# HBridge.net
KiCad netlist of a schematic drawn in Altium Designer
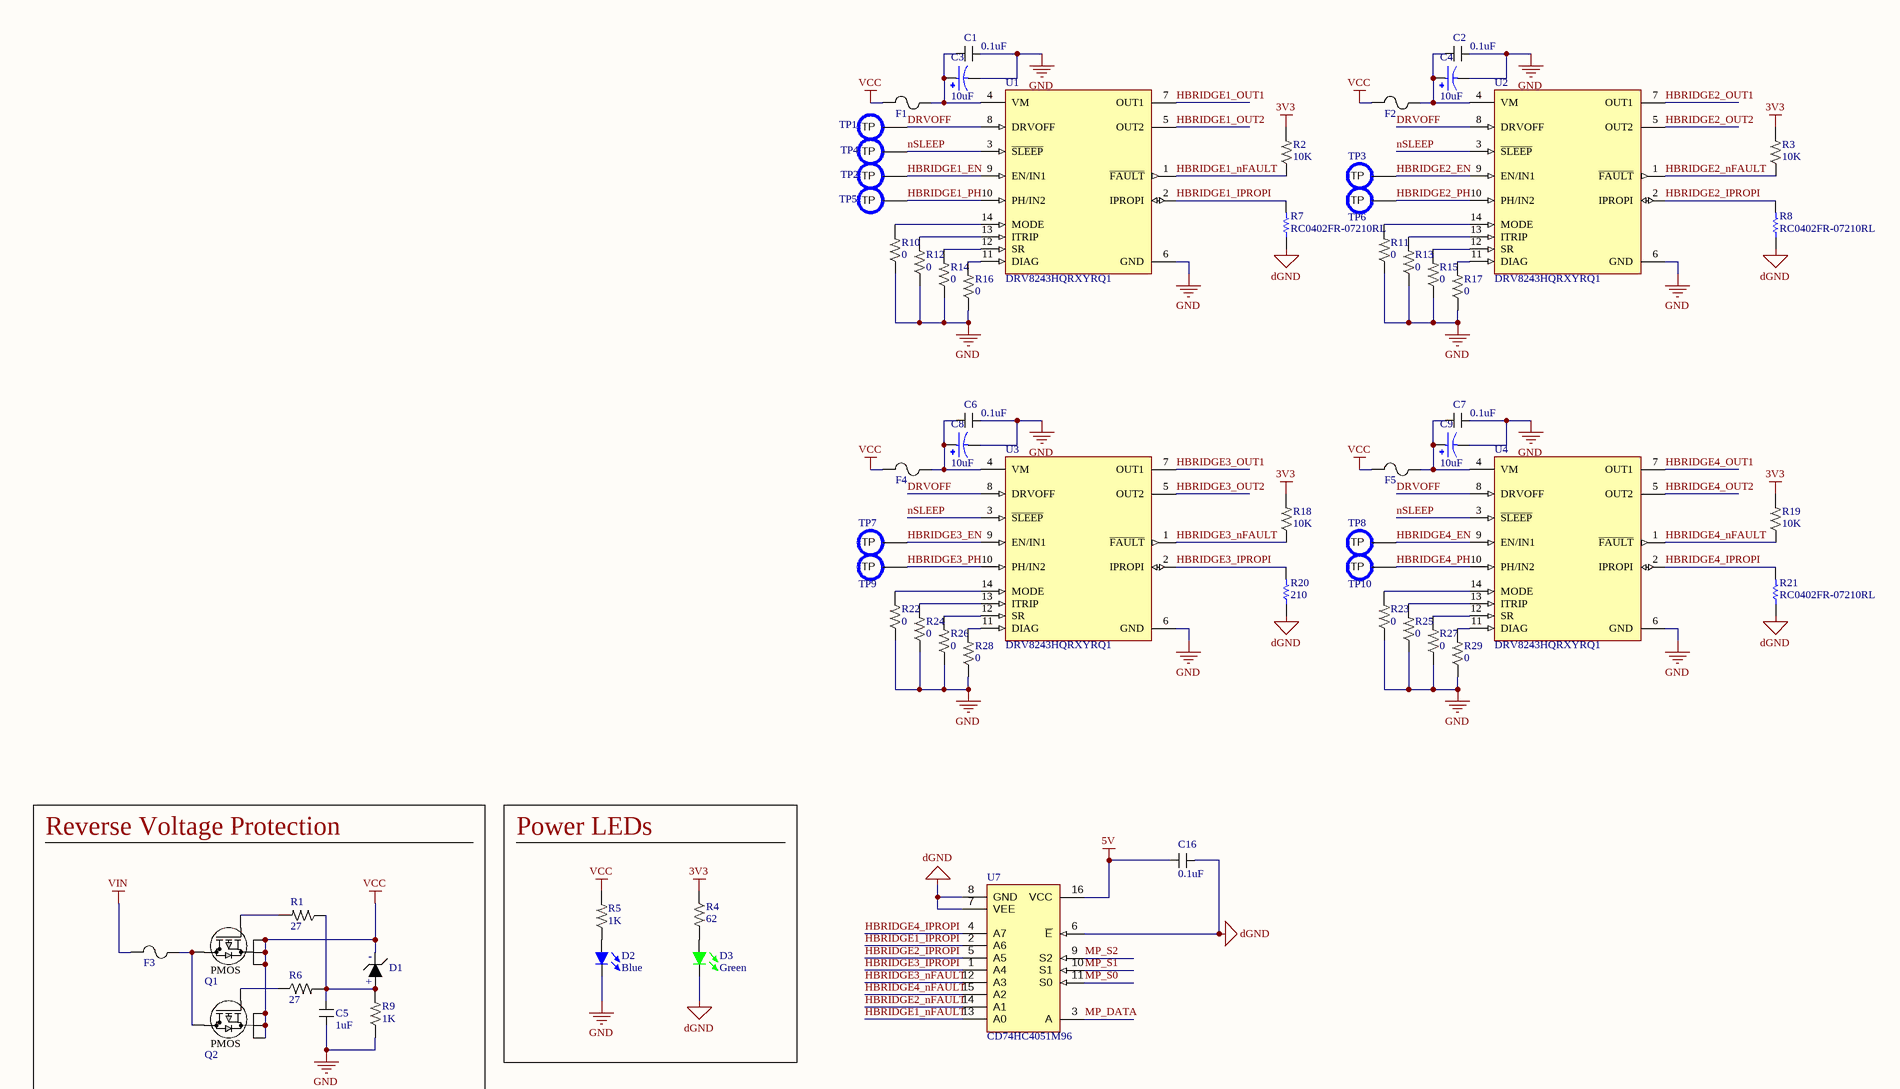
[diagram p0: HBridge.SchDoc, top left]
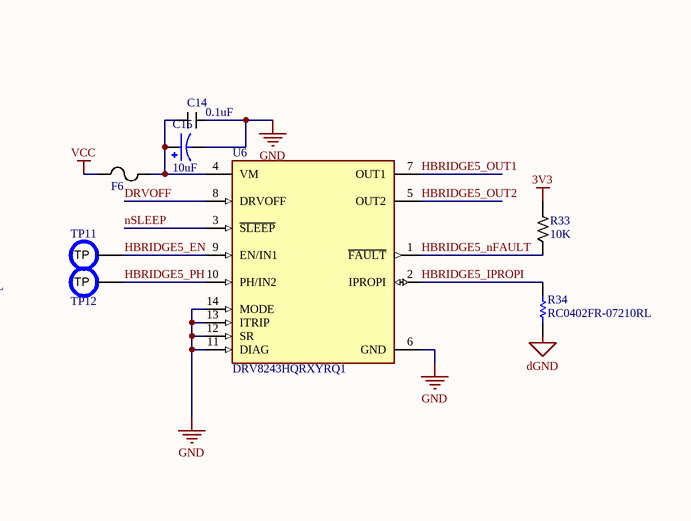
[diagram p1: HBridge.SchDoc, top right]
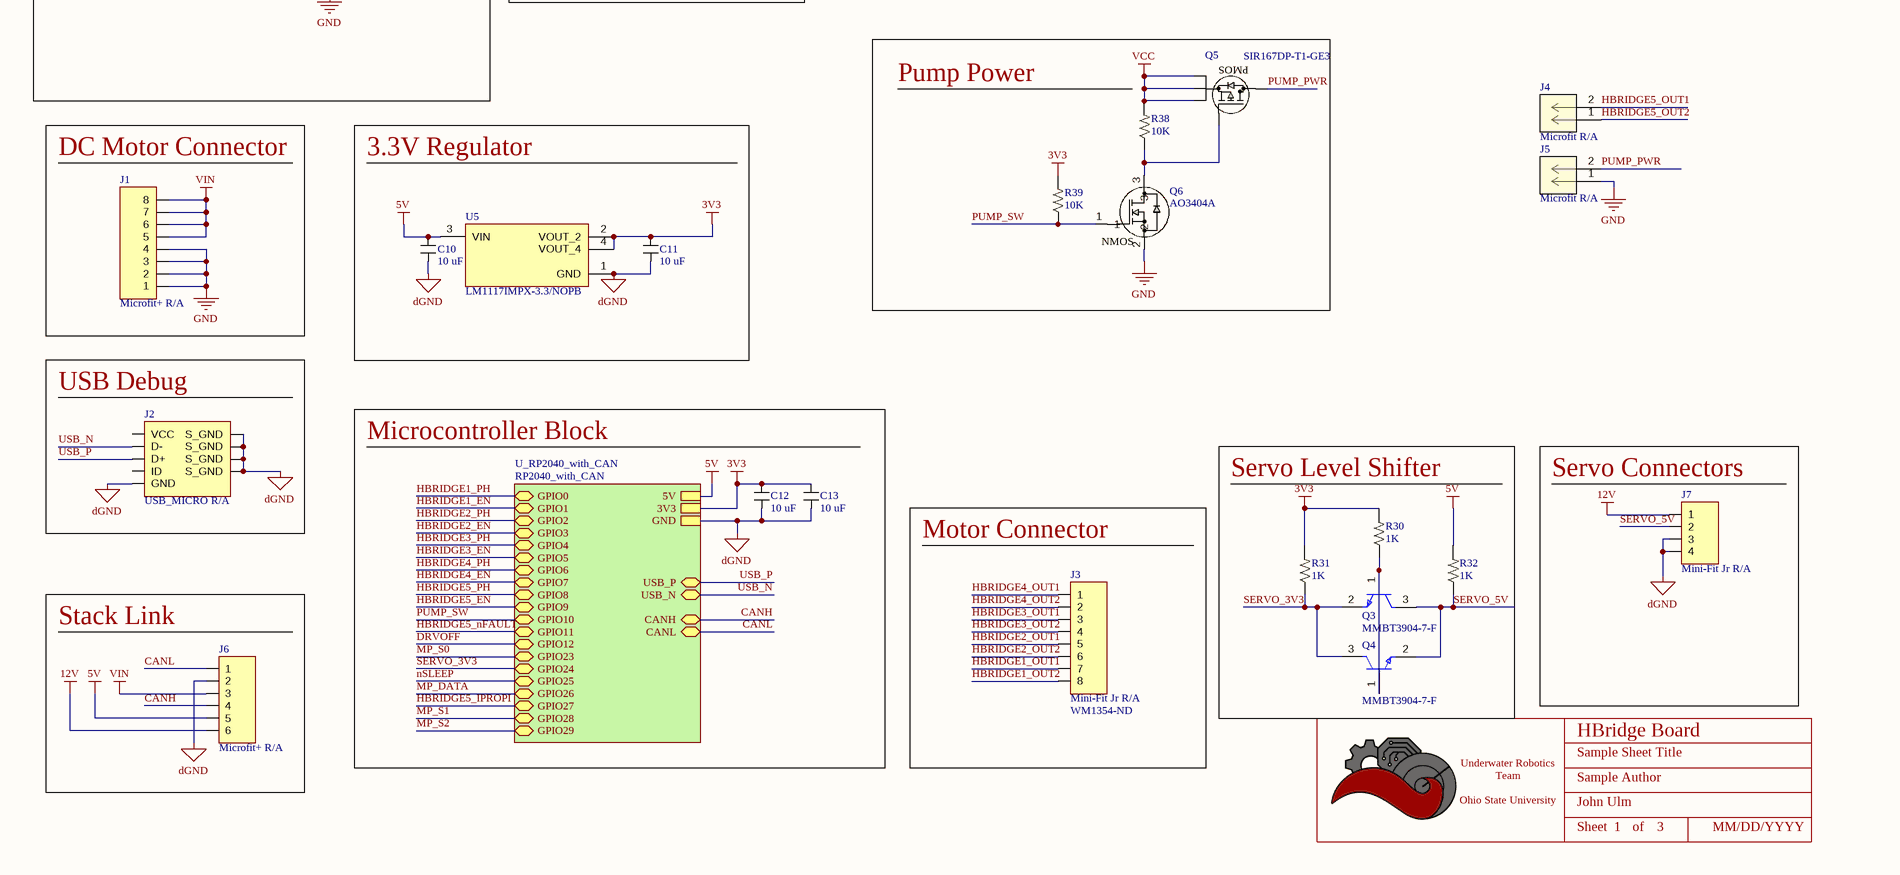
[diagram p2: HBridge.SchDoc, bottom left]

(export (version "E")
  (design (tool "Eeschema 10.0.6"))
  (components
    (comp (ref "*")
      (value "Title_Block")
      (footprint "LOGO")
      (description "UWRT Schematic Title Block Template\r\n\r\nCreated June 2021, Dylan Trainor")
      (libsource (lib "UWRT") (part "Title_Block"))
    )
    (comp (ref "C1")
      (value "0.1uF")
      (footprint "CAPACITOR_0805")
      (description "Cap 100nF 50V +/-10%\r\nCeramic 0805")
      (fields (field (name "TOLERANCE") "+/- 10%") (field (name "VOLTAGE") "50V"))
      (libsource (lib "Capacitors") (part "CAPACITOR_0.1uF_0805"))
    )
    (comp (ref "C2")
      (value "0.1uF")
      (footprint "CAPACITOR_0805")
      (description "Cap 100nF 50V +/-10%\r\nCeramic 0805")
      (fields (field (name "TOLERANCE") "+/- 10%") (field (name "VOLTAGE") "50V"))
      (libsource (lib "Capacitors") (part "CAPACITOR_0.1uF_0805"))
    )
    (comp (ref "C3")
      (value "10uF")
      (footprint "CAP_EEHZC1J100P")
      (description "10 µF 63 V Aluminum - Polymer Capacitors Radial, Can SMD 120mOhm")
      (fields (field (name "TOLERANCE") "+/- 20%") (field (name "Comment") "10uF electrolytic 63V"))
      (libsource (lib "Capacitors") (part "CAP ALUM 10UF 20% 63V SMD"))
    )
    (comp (ref "C4")
      (value "10uF")
      (footprint "CAP_EEHZC1J100P")
      (description "10 µF 63 V Aluminum - Polymer Capacitors Radial, Can SMD 120mOhm")
      (fields (field (name "TOLERANCE") "+/- 20%") (field (name "Comment") "10uF electrolytic 63V"))
      (libsource (lib "Capacitors") (part "CAP ALUM 10UF 20% 63V SMD"))
    )
    (comp (ref "C5")
      (value "1uF")
      (footprint "CAPACITOR_0603")
      (description "Cap 1uF 16V +/-10%\r\nCeramic 0603")
      (fields (field (name "TOLERANCE") "+/- 10%") (field (name "VOLTAGE") "16V"))
      (libsource (lib "Capacitors") (part "CAPACITOR_1uF_0603"))
    )
    (comp (ref "C6")
      (value "0.1uF")
      (footprint "CAPACITOR_0805")
      (description "Cap 100nF 50V +/-10%\r\nCeramic 0805")
      (fields (field (name "TOLERANCE") "+/- 10%") (field (name "VOLTAGE") "50V"))
      (libsource (lib "Capacitors") (part "CAPACITOR_0.1uF_0805"))
    )
    (comp (ref "C7")
      (value "0.1uF")
      (footprint "CAPACITOR_0805")
      (description "Cap 100nF 50V +/-10%\r\nCeramic 0805")
      (fields (field (name "TOLERANCE") "+/- 10%") (field (name "VOLTAGE") "50V"))
      (libsource (lib "Capacitors") (part "CAPACITOR_0.1uF_0805"))
    )
    (comp (ref "C8")
      (value "10uF")
      (footprint "CAP_EEHZC1J100P")
      (description "10 µF 63 V Aluminum - Polymer Capacitors Radial, Can SMD 120mOhm")
      (fields (field (name "TOLERANCE") "+/- 20%") (field (name "Comment") "10uF electrolytic 63V"))
      (libsource (lib "Capacitors") (part "CAP ALUM 10UF 20% 63V SMD"))
    )
    (comp (ref "C9")
      (value "10uF")
      (footprint "CAP_EEHZC1J100P")
      (description "10 µF 63 V Aluminum - Polymer Capacitors Radial, Can SMD 120mOhm")
      (fields (field (name "TOLERANCE") "+/- 20%") (field (name "Comment") "10uF electrolytic 63V"))
      (libsource (lib "Capacitors") (part "CAP ALUM 10UF 20% 63V SMD"))
    )
    (comp (ref "C10")
      (value "10uF Ceramic 6.3V")
      (footprint "CAPACITOR_0603")
      (description "Cap 10uF 6.3V +/-20%\r\nCeramic 0603")
      (fields
        (field (name "TOLERANCE") "+/- 20%")
        (field (name "VOLTAGE") "6.3V")
        (field (name "VALUE (UF)") "10 uF")
      )
      (libsource (lib "Capacitors") (part "CAPACITOR_10uF_0603"))
    )
    (comp (ref "C11")
      (value "10uF Ceramic 6.3V")
      (footprint "CAPACITOR_0603")
      (description "Cap 10uF 6.3V +/-20%\r\nCeramic 0603")
      (fields
        (field (name "TOLERANCE") "+/- 20%")
        (field (name "VOLTAGE") "6.3V")
        (field (name "VALUE (UF)") "10 uF")
      )
      (libsource (lib "Capacitors") (part "CAPACITOR_10uF_0603"))
    )
    (comp (ref "C12")
      (value "10uF Ceramic 6.3V")
      (footprint "CAPACITOR_0603")
      (description "Cap 10uF 6.3V +/-20%\r\nCeramic 0603")
      (fields
        (field (name "TOLERANCE") "+/- 20%")
        (field (name "VOLTAGE") "6.3V")
        (field (name "VALUE (UF)") "10 uF")
      )
      (libsource (lib "Capacitors") (part "CAPACITOR_10uF_0603"))
    )
    (comp (ref "C13")
      (value "10uF Ceramic 6.3V")
      (footprint "CAPACITOR_0603")
      (description "Cap 10uF 6.3V +/-20%\r\nCeramic 0603")
      (fields
        (field (name "TOLERANCE") "+/- 20%")
        (field (name "VOLTAGE") "6.3V")
        (field (name "VALUE (UF)") "10 uF")
      )
      (libsource (lib "Capacitors") (part "CAPACITOR_10uF_0603"))
    )
    (comp (ref "C14")
      (value "0.1uF")
      (footprint "CAPACITOR_0805")
      (description "Cap 100nF 50V +/-10%\r\nCeramic 0805")
      (fields (field (name "TOLERANCE") "+/- 10%") (field (name "VOLTAGE") "50V"))
      (libsource (lib "Capacitors") (part "CAPACITOR_0.1uF_0805"))
    )
    (comp (ref "C15")
      (value "10uF")
      (footprint "CAP_EEHZC1J100P")
      (description "10 µF 63 V Aluminum - Polymer Capacitors Radial, Can SMD 120mOhm")
      (fields (field (name "TOLERANCE") "+/- 20%") (field (name "Comment") "10uF electrolytic 63V"))
      (libsource (lib "Capacitors") (part "CAP ALUM 10UF 20% 63V SMD"))
    )
    (comp (ref "C16")
      (value "0.1uF")
      (footprint "CAPACITOR_0402")
      (description "Cap 100nF 25V +/-10%\r\nCeramic 0402")
      (fields (field (name "TOLERANCE") "+/- 10%") (field (name "VOLTAGE") "25V"))
      (libsource (lib "Capacitors") (part "CAPACITOR_0.1uF_0402"))
    )
    (comp (ref "D1")
      (value "Zener_Diode_10V_410mW")
      (footprint "SOD-123")
      (description "Zener Diode ¦ 10 V ¦ 410 mW ¦ SOD 123")
      (fields (field (name "POWER") "410mW"))
      (libsource (lib "Diodes") (part "Zener_Diode_10V_410mW"))
    )
    (comp (ref "D2")
      (value "150060BS75000")
      (footprint "LED_0603")
      (description "LED Blue Vf= 3.2V If = 0.020A\r\n150060BS75000")
      (fields (field (name "COLOR") "Blue"))
      (libsource (lib "Diodes") (part "LED_Blue_0603"))
    )
    (comp (ref "D3")
      (value "150060GS75000")
      (footprint "LED_0603")
      (description "LED Green Vf= 3.2V If = 0.025A\r\n150060GS75000")
      (fields (field (name "COLOR") "Green"))
      (libsource (lib "Diodes") (part "LED_Green_0603_3.2V"))
    )
    (comp (ref "F1")
      (value "0685H9150-01")
      (footprint "0501Series_LTF")
      (description "Bel Fuse  ¦ 15A ¦ 32V DC ¦ SMD ¦ Fast Blow ¦ 1206")
      (libsource (lib "Fuses") (part "Bel Fuse 15A"))
    )
    (comp (ref "F2")
      (value "0685H9150-01")
      (footprint "0501Series_LTF")
      (description "Bel Fuse  ¦ 15A ¦ 32V DC ¦ SMD ¦ Fast Blow ¦ 1206")
      (libsource (lib "Fuses") (part "Bel Fuse 15A"))
    )
    (comp (ref "F3")
      (value "1245HC60-RTR")
      (footprint "2-SMD Fuse")
      (description "Eaton  ¦ 60A ¦ 80V DC ¦ SMD ¦ Fast Blow ¦ 2-SMD")
      (libsource (lib "Fuses") (part "Eaton 60A Fuse"))
    )
    (comp (ref "F4")
      (value "0685H9150-01")
      (footprint "0501Series_LTF")
      (description "Bel Fuse  ¦ 15A ¦ 32V DC ¦ SMD ¦ Fast Blow ¦ 1206")
      (libsource (lib "Fuses") (part "Bel Fuse 15A"))
    )
    (comp (ref "F5")
      (value "0685H9150-01")
      (footprint "0501Series_LTF")
      (description "Bel Fuse  ¦ 15A ¦ 32V DC ¦ SMD ¦ Fast Blow ¦ 1206")
      (libsource (lib "Fuses") (part "Bel Fuse 15A"))
    )
    (comp (ref "F6")
      (value "0685H9150-01")
      (footprint "0501Series_LTF")
      (description "Bel Fuse  ¦ 15A ¦ 32V DC ¦ SMD ¦ Fast Blow ¦ 1206")
      (libsource (lib "Fuses") (part "Bel Fuse 15A"))
    )
    (comp (ref "J1")
      (value "Microfit+ R/A")
      (footprint "CONN_MOLEX_MICROFIT+_8POS_R/A")
      (description "Molex Microfit+ \r\n212528 8 POS R/A Black")
      (fields (field (name "MANUFACTURER") "Molex"))
      (libsource (lib "Connectors") (part "CONN_MOLEX_MICROFIT+_8POS_R/A"))
    )
    (comp (ref "J2")
      (value "USB_MICRO R/A")
      (footprint "CONN_MINIUSB")
      (description "Amphenol Micro USB-B\r\nUSB2.0 5 Pin Right Angle SMD")
      (fields (field (name "MANUFACTURER") "Amphenol"))
      (libsource (lib "Connectors") (part "CONN_MICROUSB"))
    )
    (comp (ref "J3")
      (value "Mini-Fit Jr R/A")
      (footprint "CONN_MOLEX_MINIFIT JR_8 POS_R/A")
      (description "Molex Minifit Jr. 5569 \r\n8 Pos R/A Natural")
      (fields (field (name "MANUFACTURER") "Molex") (field (name "SUPPLIER PART NUMBER 1") "WM1354-ND"))
      (libsource (lib "Connectors") (part "CONN_MOLEX_MINIFIT JR_8POS_R/A"))
    )
    (comp (ref "J4")
      (value "Microfit R/A")
      (footprint "CONN_MOLEX_MICROFIT_2 POS_R/A")
      (description "CONN HEADER R/A 2POS")
      (fields (field (name "MANUFACTURER") "Molex"))
      (libsource (lib "Connectors") (part "CONN_MOLEX_MICROFIT_2 POS_R/A"))
    )
    (comp (ref "J5")
      (value "Microfit R/A")
      (footprint "CONN_MOLEX_MICROFIT_2 POS_R/A")
      (description "CONN HEADER R/A 2POS")
      (fields (field (name "MANUFACTURER") "Molex"))
      (libsource (lib "Connectors") (part "CONN_MOLEX_MICROFIT_2 POS_R/A"))
    )
    (comp (ref "J6")
      (value "Microfit+ R/A")
      (footprint "CONN_MOLEX_MICROFIT_6_POS_R/A")
      (description "Molex Microfit+ \r\n212528 6 POS R/A Black")
      (fields (field (name "MANUFACTURER") "Molex"))
      (libsource (lib "Connectors") (part "CONN_MOLEX_MICROFIT+_6POS_R/A"))
    )
    (comp (ref "J7")
      (value "Mini-Fit Jr R/A")
      (footprint "CONN_MOLEX_MINIFIT JR_4 POS_R/A")
      (description "Molex Minifit Jr. 5569 \r\n4 Pos R/A Natural")
      (fields (field (name "MANUFACTURER") "Molex"))
      (libsource (lib "Connectors") (part "CONN_MOLEX_MINIFIT JR_4POS_R/A"))
    )
    (comp (ref "Q1")
      (value "MOSFET P-Ch 30V 60A SO-8")
      (footprint "MOSFET_7DP-T1-GE3_VIS")
      (description "P-Channel 30 V 60A (Tc) 65.8W (Tc) Surface Mount PowerPAK® SO-8")
      (fields (field (name "MANUFACTURER_PART_NUMBER") "SIR167DP-T1-GE3"))
      (libsource (lib "Transistors") (part "SIR167DP-T1-GE3"))
    )
    (comp (ref "Q2")
      (value "MOSFET P-Ch 30V 60A SO-8")
      (footprint "MOSFET_7DP-T1-GE3_VIS")
      (description "P-Channel 30 V 60A (Tc) 65.8W (Tc) Surface Mount PowerPAK® SO-8")
      (fields (field (name "MANUFACTURER_PART_NUMBER") "SIR167DP-T1-GE3"))
      (libsource (lib "Transistors") (part "SIR167DP-T1-GE3"))
    )
    (comp (ref "Q3")
      (value "MMBT3904-7-F")
      (footprint "FP-SOT23-IPC_A")
      (description "TRANS NPN 40V 0.2A SMD SOT23-3")
      (libsource (lib "Altium Content Vault") (part "b44e953556f554d0102664c7d152cb4"))
    )
    (comp (ref "Q4")
      (value "MMBT3904-7-F")
      (footprint "FP-SOT23-IPC_A")
      (description "TRANS NPN 40V 0.2A SMD SOT23-3")
      (libsource (lib "Altium Content Vault") (part "b44e953556f554d0102664c7d152cb4"))
    )
    (comp (ref "Q5")
      (value "SIR167DP-T1-GE3")
      (footprint "MOSFET_7DP-T1-GE3_VIS")
      (description "P-Channel 30 V 60A (Tc) 65.8W (Tc) Surface Mount PowerPAK® SO-8")
      (libsource (lib "Transistors") (part "SIR167DP-T1-GE3"))
    )
    (comp (ref "Q6")
      (value "AO3404A")
      (footprint "SOT-23-3")
      (description "N-Channel 30 V 5.8A (Ta) 1.4W (Ta) Surface Mount SOT-23-3")
      (libsource (lib "Transistors") (part "AO3404A"))
    )
    (comp (ref "R1")
      (value "27 Ohm 5% 1/8W")
      (footprint "RESISTOR_0603")
      (description "RES 27 OHM 5% 1/8W 0603")
      (fields (field (name "TOLERANCE") "+/- 5%") (field (name "VALUE  (OHMS)") "27"))
      (libsource (lib "Resistors") (part "RESISTOR_27_0603"))
    )
    (comp (ref "R2")
      (value "10k Ohm 1% 1/16W")
      (footprint "RESISTOR_0402")
      (description "RES 10k OHM 1% 1/16W 0402")
      (fields (field (name "TOLERANCE") "+/- 1%") (field (name "VALUE  (OHMS)") "10K"))
      (libsource (lib "Resistors") (part "RESISTOR_10K_0402"))
    )
    (comp (ref "R3")
      (value "10k Ohm 1% 1/16W")
      (footprint "RESISTOR_0402")
      (description "RES 10k OHM 1% 1/16W 0402")
      (fields (field (name "TOLERANCE") "+/- 1%") (field (name "VALUE  (OHMS)") "10K"))
      (libsource (lib "Resistors") (part "RESISTOR_10K_0402"))
    )
    (comp (ref "R4")
      (value "62 Ohm 1% 1/4W")
      (footprint "RESISTOR_0603")
      (description "RES SMD 62 OHM 1% 1/4W 0603")
      (fields (field (name "TOLERANCE") "+/- 1%") (field (name "VALUE  (OHMS)") "62"))
      (libsource (lib "Resistors") (part "RESISTOR_62_0603"))
    )
    (comp (ref "R5")
      (value "1k Ohm 5% 1/8W")
      (footprint "RESISTOR_0603")
      (description "RES 1k OHM 5% 1/8W 0603")
      (fields (field (name "TOLERANCE") "+/- 5%") (field (name "VALUE  (OHMS)") "1K"))
      (libsource (lib "Resistors") (part "RESISTOR_1K_0603"))
    )
    (comp (ref "R6")
      (value "27 Ohm 5% 1/8W")
      (footprint "RESISTOR_0603")
      (description "RES 27 OHM 5% 1/8W 0603")
      (fields (field (name "TOLERANCE") "+/- 5%") (field (name "VALUE  (OHMS)") "27"))
      (libsource (lib "Resistors") (part "RESISTOR_27_0603"))
    )
    (comp (ref "R7")
      (value "RC0402FR-07210RL")
      (footprint "RESC1005X40X25LL05T10")
      (fields (field (name "MANUFACTURER") "Yageo"))
      (libsource (lib "Altium Content Vault") (part "RES"))
    )
    (comp (ref "R8")
      (value "RC0402FR-07210RL")
      (footprint "RESC1005X40X25LL05T10")
      (fields (field (name "MANUFACTURER") "Yageo"))
      (libsource (lib "Altium Content Vault") (part "RES"))
    )
    (comp (ref "R9")
      (value "1k Ohm 5% 1/8W")
      (footprint "RESISTOR_0603")
      (description "RES 1k OHM 5% 1/8W 0603")
      (fields (field (name "TOLERANCE") "+/- 5%") (field (name "VALUE  (OHMS)") "1K"))
      (libsource (lib "Resistors") (part "RESISTOR_1K_0603"))
    )
    (comp (ref "R10")
      (value "0 Ohm 1% 1/16W")
      (footprint "RESISTOR_0402")
      (description "RES 0 OHM 1% 1/16W 0402")
      (fields (field (name "TOLERANCE") "+/- 1%") (field (name "VALUE  (OHMS)") "0"))
      (libsource (lib "Resistors") (part "RESISTOR_0_0402"))
    )
    (comp (ref "R11")
      (value "0 Ohm 1% 1/16W")
      (footprint "RESISTOR_0402")
      (description "RES 0 OHM 1% 1/16W 0402")
      (fields (field (name "TOLERANCE") "+/- 1%") (field (name "VALUE  (OHMS)") "0"))
      (libsource (lib "Resistors") (part "RESISTOR_0_0402"))
    )
    (comp (ref "R12")
      (value "0 Ohm 1% 1/16W")
      (footprint "RESISTOR_0402")
      (description "RES 0 OHM 1% 1/16W 0402")
      (fields (field (name "TOLERANCE") "+/- 1%") (field (name "VALUE  (OHMS)") "0"))
      (libsource (lib "Resistors") (part "RESISTOR_0_0402"))
    )
    (comp (ref "R13")
      (value "0 Ohm 1% 1/16W")
      (footprint "RESISTOR_0402")
      (description "RES 0 OHM 1% 1/16W 0402")
      (fields (field (name "TOLERANCE") "+/- 1%") (field (name "VALUE  (OHMS)") "0"))
      (libsource (lib "Resistors") (part "RESISTOR_0_0402"))
    )
    (comp (ref "R14")
      (value "0 Ohm 1% 1/16W")
      (footprint "RESISTOR_0402")
      (description "RES 0 OHM 1% 1/16W 0402")
      (fields (field (name "TOLERANCE") "+/- 1%") (field (name "VALUE  (OHMS)") "0"))
      (libsource (lib "Resistors") (part "RESISTOR_0_0402"))
    )
    (comp (ref "R15")
      (value "0 Ohm 1% 1/16W")
      (footprint "RESISTOR_0402")
      (description "RES 0 OHM 1% 1/16W 0402")
      (fields (field (name "TOLERANCE") "+/- 1%") (field (name "VALUE  (OHMS)") "0"))
      (libsource (lib "Resistors") (part "RESISTOR_0_0402"))
    )
    (comp (ref "R16")
      (value "0 Ohm 1% 1/16W")
      (footprint "RESISTOR_0402")
      (description "RES 0 OHM 1% 1/16W 0402")
      (fields (field (name "TOLERANCE") "+/- 1%") (field (name "VALUE  (OHMS)") "0"))
      (libsource (lib "Resistors") (part "RESISTOR_0_0402"))
    )
    (comp (ref "R17")
      (value "0 Ohm 1% 1/16W")
      (footprint "RESISTOR_0402")
      (description "RES 0 OHM 1% 1/16W 0402")
      (fields (field (name "TOLERANCE") "+/- 1%") (field (name "VALUE  (OHMS)") "0"))
      (libsource (lib "Resistors") (part "RESISTOR_0_0402"))
    )
    (comp (ref "R18")
      (value "10k Ohm 1% 1/16W")
      (footprint "RESISTOR_0402")
      (description "RES 10k OHM 1% 1/16W 0402")
      (fields (field (name "TOLERANCE") "+/- 1%") (field (name "VALUE  (OHMS)") "10K"))
      (libsource (lib "Resistors") (part "RESISTOR_10K_0402"))
    )
    (comp (ref "R19")
      (value "10k Ohm 1% 1/16W")
      (footprint "RESISTOR_0402")
      (description "RES 10k OHM 1% 1/16W 0402")
      (fields (field (name "TOLERANCE") "+/- 1%") (field (name "VALUE  (OHMS)") "10K"))
      (libsource (lib "Resistors") (part "RESISTOR_10K_0402"))
    )
    (comp (ref "R20")
      (value "210")
      (footprint "RESC1005X40X25LL05T10")
      (fields (field (name "PART NUMBER") "RC0402FR-07210RL") (field (name "MANUFACTURER") "Yageo"))
      (libsource (lib "Altium Content Vault") (part "RES"))
    )
    (comp (ref "R21")
      (value "RC0402FR-07210RL")
      (footprint "RESC1005X40X25LL05T10")
      (fields (field (name "MANUFACTURER") "Yageo"))
      (libsource (lib "Altium Content Vault") (part "RES"))
    )
    (comp (ref "R22")
      (value "0 Ohm 1% 1/16W")
      (footprint "RESISTOR_0402")
      (description "RES 0 OHM 1% 1/16W 0402")
      (fields (field (name "TOLERANCE") "+/- 1%") (field (name "VALUE  (OHMS)") "0"))
      (libsource (lib "Resistors") (part "RESISTOR_0_0402"))
    )
    (comp (ref "R23")
      (value "0 Ohm 1% 1/16W")
      (footprint "RESISTOR_0402")
      (description "RES 0 OHM 1% 1/16W 0402")
      (fields (field (name "TOLERANCE") "+/- 1%") (field (name "VALUE  (OHMS)") "0"))
      (libsource (lib "Resistors") (part "RESISTOR_0_0402"))
    )
    (comp (ref "R24")
      (value "0 Ohm 1% 1/16W")
      (footprint "RESISTOR_0402")
      (description "RES 0 OHM 1% 1/16W 0402")
      (fields (field (name "TOLERANCE") "+/- 1%") (field (name "VALUE  (OHMS)") "0"))
      (libsource (lib "Resistors") (part "RESISTOR_0_0402"))
    )
    (comp (ref "R25")
      (value "0 Ohm 1% 1/16W")
      (footprint "RESISTOR_0402")
      (description "RES 0 OHM 1% 1/16W 0402")
      (fields (field (name "TOLERANCE") "+/- 1%") (field (name "VALUE  (OHMS)") "0"))
      (libsource (lib "Resistors") (part "RESISTOR_0_0402"))
    )
    (comp (ref "R26")
      (value "0 Ohm 1% 1/16W")
      (footprint "RESISTOR_0402")
      (description "RES 0 OHM 1% 1/16W 0402")
      (fields (field (name "TOLERANCE") "+/- 1%") (field (name "VALUE  (OHMS)") "0"))
      (libsource (lib "Resistors") (part "RESISTOR_0_0402"))
    )
    (comp (ref "R27")
      (value "0 Ohm 1% 1/16W")
      (footprint "RESISTOR_0402")
      (description "RES 0 OHM 1% 1/16W 0402")
      (fields (field (name "TOLERANCE") "+/- 1%") (field (name "VALUE  (OHMS)") "0"))
      (libsource (lib "Resistors") (part "RESISTOR_0_0402"))
    )
    (comp (ref "R28")
      (value "0 Ohm 1% 1/16W")
      (footprint "RESISTOR_0402")
      (description "RES 0 OHM 1% 1/16W 0402")
      (fields (field (name "TOLERANCE") "+/- 1%") (field (name "VALUE  (OHMS)") "0"))
      (libsource (lib "Resistors") (part "RESISTOR_0_0402"))
    )
    (comp (ref "R29")
      (value "0 Ohm 1% 1/16W")
      (footprint "RESISTOR_0402")
      (description "RES 0 OHM 1% 1/16W 0402")
      (fields (field (name "TOLERANCE") "+/- 1%") (field (name "VALUE  (OHMS)") "0"))
      (libsource (lib "Resistors") (part "RESISTOR_0_0402"))
    )
    (comp (ref "R30")
      (value "1k Ohm 5% 1/8W")
      (footprint "RESISTOR_0603")
      (description "RES 1k OHM 5% 1/8W 0603")
      (fields (field (name "TOLERANCE") "+/- 5%") (field (name "VALUE  (OHMS)") "1K"))
      (libsource (lib "Resistors") (part "RESISTOR_1K_0603"))
    )
    (comp (ref "R31")
      (value "1k Ohm 5% 1/8W")
      (footprint "RESISTOR_0603")
      (description "RES 1k OHM 5% 1/8W 0603")
      (fields (field (name "TOLERANCE") "+/- 5%") (field (name "VALUE  (OHMS)") "1K"))
      (libsource (lib "Resistors") (part "RESISTOR_1K_0603"))
    )
    (comp (ref "R32")
      (value "1k Ohm 5% 1/8W")
      (footprint "RESISTOR_0603")
      (description "RES 1k OHM 5% 1/8W 0603")
      (fields (field (name "TOLERANCE") "+/- 5%") (field (name "VALUE  (OHMS)") "1K"))
      (libsource (lib "Resistors") (part "RESISTOR_1K_0603"))
    )
    (comp (ref "R33")
      (value "10k Ohm 1% 1/16W")
      (footprint "RESISTOR_0402")
      (description "RES 10k OHM 1% 1/16W 0402")
      (fields (field (name "TOLERANCE") "+/- 1%") (field (name "VALUE  (OHMS)") "10K"))
      (libsource (lib "Resistors") (part "RESISTOR_10K_0402"))
    )
    (comp (ref "R34")
      (value "RC0402FR-07210RL")
      (footprint "RESC1005X40X25LL05T10")
      (fields (field (name "MANUFACTURER") "Yageo"))
      (libsource (lib "Altium Content Vault") (part "RES"))
    )
    (comp (ref "R38")
      (value "10k Ohm 5% 1/10W")
      (footprint "RESISTOR_0603")
      (description "RES 10k OHM 5% 1/10W 0603")
      (fields (field (name "TOLERANCE") "+/- 5%") (field (name "VALUE  (OHMS)") "10K"))
      (libsource (lib "Resistors") (part "RESISTOR_10K_0603"))
    )
    (comp (ref "R39")
      (value "10k Ohm 5% 1/10W")
      (footprint "RESISTOR_0603")
      (description "RES 10k OHM 5% 1/10W 0603")
      (fields (field (name "TOLERANCE") "+/- 5%") (field (name "VALUE  (OHMS)") "10K"))
      (libsource (lib "Resistors") (part "RESISTOR_10K_0603"))
    )
    (comp (ref "TP1")
      (value "PCB Test Point")
      (footprint "TESTPOINT_1.2MM")
      (libsource (lib "Connectors") (part "TESTPOINT"))
    )
    (comp (ref "TP2")
      (value "PCB Test Point")
      (footprint "TESTPOINT_1.2MM")
      (libsource (lib "Connectors") (part "TESTPOINT"))
    )
    (comp (ref "TP3")
      (value "PCB Test Point")
      (footprint "TESTPOINT_1.2MM")
      (libsource (lib "Connectors") (part "TESTPOINT"))
    )
    (comp (ref "TP4")
      (value "PCB Test Point")
      (footprint "TESTPOINT_1.2MM")
      (libsource (lib "Connectors") (part "TESTPOINT"))
    )
    (comp (ref "TP5")
      (value "PCB Test Point")
      (footprint "TESTPOINT_1.2MM")
      (libsource (lib "Connectors") (part "TESTPOINT"))
    )
    (comp (ref "TP6")
      (value "PCB Test Point")
      (footprint "TESTPOINT_1.2MM")
      (libsource (lib "Connectors") (part "TESTPOINT"))
    )
    (comp (ref "TP7")
      (value "PCB Test Point")
      (footprint "TESTPOINT_1.2MM")
      (libsource (lib "Connectors") (part "TESTPOINT"))
    )
    (comp (ref "TP8")
      (value "PCB Test Point")
      (footprint "TESTPOINT_1.2MM")
      (libsource (lib "Connectors") (part "TESTPOINT"))
    )
    (comp (ref "TP9")
      (value "PCB Test Point")
      (footprint "TESTPOINT_1.2MM")
      (libsource (lib "Connectors") (part "TESTPOINT"))
    )
    (comp (ref "TP10")
      (value "PCB Test Point")
      (footprint "TESTPOINT_1.2MM")
      (libsource (lib "Connectors") (part "TESTPOINT"))
    )
    (comp (ref "TP11")
      (value "PCB Test Point")
      (footprint "TESTPOINT_1.2MM")
      (libsource (lib "Connectors") (part "TESTPOINT"))
    )
    (comp (ref "TP12")
      (value "PCB Test Point")
      (footprint "TESTPOINT_1.2MM")
      (libsource (lib "Connectors") (part "TESTPOINT"))
    )
    (comp (ref "U1")
      (value "DRV8243HQRXYRQ1")
      (footprint "FP-RXY0014A-MFG")
      (libsource (lib "Integrated Circuits") (part "DRV8243HQRXYRQ1"))
    )
    (comp (ref "U2")
      (value "DRV8243HQRXYRQ1")
      (footprint "FP-RXY0014A-MFG")
      (libsource (lib "Integrated Circuits") (part "DRV8243HQRXYRQ1"))
    )
    (comp (ref "U3")
      (value "DRV8243HQRXYRQ1")
      (footprint "FP-RXY0014A-MFG")
      (libsource (lib "Integrated Circuits") (part "DRV8243HQRXYRQ1"))
    )
    (comp (ref "U4")
      (value "DRV8243HQRXYRQ1")
      (footprint "FP-RXY0014A-MFG")
      (libsource (lib "Integrated Circuits") (part "DRV8243HQRXYRQ1"))
    )
    (comp (ref "U5")
      (value "LM1117IMPX-3.3/NOPB")
      (footprint "SOT-223-4")
      (description "800-mA 15-V linear voltage regulator 4-SOT-223 -40 to 125")
      (fields (field (name "MF") "Texas Instruments"))
      (libsource (lib "Integrated Circuits") (part "LM1117IMPX-3.3/NOPB"))
    )
    (comp (ref "U6")
      (value "DRV8243HQRXYRQ1")
      (footprint "FP-RXY0014A-MFG")
      (libsource (lib "Integrated Circuits") (part "DRV8243HQRXYRQ1"))
    )
    (comp (ref "U7")
      (value "CD74HC4051M96")
      (footprint "D0016A_M")
      (description "High Speed CMOS 8-Channel Analog Multiplexer/Demultiplexer, D0016A, LARGE T&R")
      (fields
        (field (name "GENERIC PART NUMBER") "CD74HC4051")
        (field (name "MANUFACTURER") "Texas Instruments")
      )
      (libsource (lib "Altium Content Vault") (part "TI-CD74HCX4051-16"))
    )
  )
  (nets
    (net (code "1") (name "/CANH") (class "Default")
      (node (ref "J6") (pin "4") (pinfunction "4_4") (pintype "passive"))
    )
    (net (code "2") (name "/CANL") (class "Default")
      (node (ref "J6") (pin "1") (pinfunction "1_1") (pintype "passive"))
    )
    (net (code "3") (name "/DRVOFF") (class "Default")
      (node (ref "TP1") (pin "TP") (pinfunction "TP_TP") (pintype "passive"))
      (node (ref "U1") (pin "8") (pinfunction "DRVOFF_8") (pintype "input"))
      (node (ref "U2") (pin "8") (pinfunction "DRVOFF_8") (pintype "input"))
      (node (ref "U3") (pin "8") (pinfunction "DRVOFF_8") (pintype "input"))
      (node (ref "U4") (pin "8") (pinfunction "DRVOFF_8") (pintype "input"))
      (node (ref "U6") (pin "8") (pinfunction "DRVOFF_8") (pintype "input"))
    )
    (net (code "4") (name "/HBRIDGE1_EN") (class "Default")
      (node (ref "TP2") (pin "TP") (pinfunction "TP_TP") (pintype "passive"))
      (node (ref "U1") (pin "9") (pinfunction "EN/IN1_9") (pintype "input"))
    )
    (net (code "5") (name "/HBRIDGE1_IPROPI") (class "Default")
      (node (ref "R7") (pin "2") (pinfunction "2_2") (pintype "passive"))
      (node (ref "U1") (pin "2") (pinfunction "IPROPI_2") (pintype "bidirectional"))
      (node (ref "U7") (pin "2") (pinfunction "A6_2") (pintype "passive"))
    )
    (net (code "6") (name "/HBRIDGE1_OUT1") (class "Default")
      (node (ref "J3") (pin "7") (pinfunction "7_7") (pintype "passive"))
      (node (ref "U1") (pin "7") (pinfunction "OUT1_7") (pintype "passive"))
    )
    (net (code "7") (name "/HBRIDGE1_OUT2") (class "Default")
      (node (ref "J3") (pin "8") (pinfunction "8_8") (pintype "passive"))
      (node (ref "U1") (pin "5") (pinfunction "OUT2_5") (pintype "passive"))
    )
    (net (code "8") (name "/HBRIDGE1_PH") (class "Default")
      (node (ref "TP5") (pin "TP") (pinfunction "TP_TP") (pintype "passive"))
      (node (ref "U1") (pin "10") (pinfunction "PH/IN2_10") (pintype "input"))
    )
    (net (code "9") (name "/HBRIDGE1_nFAULT") (class "Default")
      (node (ref "R2") (pin "2") (pinfunction "2_2") (pintype "passive"))
      (node (ref "U1") (pin "1") (pinfunction "~{FAULT}_1") (pintype "output"))
      (node (ref "U7") (pin "13") (pinfunction "A0_13") (pintype "passive"))
    )
    (net (code "10") (name "/HBRIDGE2_EN") (class "Default")
      (node (ref "TP3") (pin "TP") (pinfunction "TP_TP") (pintype "passive"))
      (node (ref "U2") (pin "9") (pinfunction "EN/IN1_9") (pintype "input"))
    )
    (net (code "11") (name "/HBRIDGE2_IPROPI") (class "Default")
      (node (ref "R8") (pin "2") (pinfunction "2_2") (pintype "passive"))
      (node (ref "U2") (pin "2") (pinfunction "IPROPI_2") (pintype "bidirectional"))
      (node (ref "U7") (pin "5") (pinfunction "A5_5") (pintype "passive"))
    )
    (net (code "12") (name "/HBRIDGE2_OUT1") (class "Default")
      (node (ref "J3") (pin "5") (pinfunction "5_5") (pintype "passive"))
      (node (ref "U2") (pin "7") (pinfunction "OUT1_7") (pintype "passive"))
    )
    (net (code "13") (name "/HBRIDGE2_OUT2") (class "Default")
      (node (ref "J3") (pin "6") (pinfunction "6_6") (pintype "passive"))
      (node (ref "U2") (pin "5") (pinfunction "OUT2_5") (pintype "passive"))
    )
    (net (code "14") (name "/HBRIDGE2_PH") (class "Default")
      (node (ref "TP6") (pin "TP") (pinfunction "TP_TP") (pintype "passive"))
      (node (ref "U2") (pin "10") (pinfunction "PH/IN2_10") (pintype "input"))
    )
    (net (code "15") (name "/HBRIDGE2_nFAULT") (class "Default")
      (node (ref "R3") (pin "2") (pinfunction "2_2") (pintype "passive"))
      (node (ref "U2") (pin "1") (pinfunction "~{FAULT}_1") (pintype "output"))
      (node (ref "U7") (pin "14") (pinfunction "A1_14") (pintype "passive"))
    )
    (net (code "16") (name "/HBRIDGE3_EN") (class "Default")
      (node (ref "TP7") (pin "TP") (pinfunction "TP_TP") (pintype "passive"))
      (node (ref "U3") (pin "9") (pinfunction "EN/IN1_9") (pintype "input"))
    )
    (net (code "17") (name "/HBRIDGE3_IPROPI") (class "Default")
      (node (ref "R20") (pin "2") (pinfunction "2_2") (pintype "passive"))
      (node (ref "U3") (pin "2") (pinfunction "IPROPI_2") (pintype "bidirectional"))
      (node (ref "U7") (pin "1") (pinfunction "A4_1") (pintype "passive"))
    )
    (net (code "18") (name "/HBRIDGE3_OUT1") (class "Default")
      (node (ref "J3") (pin "3") (pinfunction "3_3") (pintype "passive"))
      (node (ref "U3") (pin "7") (pinfunction "OUT1_7") (pintype "passive"))
    )
    (net (code "19") (name "/HBRIDGE3_OUT2") (class "Default")
      (node (ref "J3") (pin "4") (pinfunction "4_4") (pintype "passive"))
      (node (ref "U3") (pin "5") (pinfunction "OUT2_5") (pintype "passive"))
    )
    (net (code "20") (name "/HBRIDGE3_PH") (class "Default")
      (node (ref "TP9") (pin "TP") (pinfunction "TP_TP") (pintype "passive"))
      (node (ref "U3") (pin "10") (pinfunction "PH/IN2_10") (pintype "input"))
    )
    (net (code "21") (name "/HBRIDGE3_nFAULT") (class "Default")
      (node (ref "R18") (pin "2") (pinfunction "2_2") (pintype "passive"))
      (node (ref "U3") (pin "1") (pinfunction "~{FAULT}_1") (pintype "output"))
      (node (ref "U7") (pin "12") (pinfunction "A3_12") (pintype "passive"))
    )
    (net (code "22") (name "/HBRIDGE4_EN") (class "Default")
      (node (ref "TP8") (pin "TP") (pinfunction "TP_TP") (pintype "passive"))
      (node (ref "U4") (pin "9") (pinfunction "EN/IN1_9") (pintype "input"))
    )
    (net (code "23") (name "/HBRIDGE4_IPROPI") (class "Default")
      (node (ref "R21") (pin "2") (pinfunction "2_2") (pintype "passive"))
      (node (ref "U4") (pin "2") (pinfunction "IPROPI_2") (pintype "bidirectional"))
      (node (ref "U7") (pin "4") (pinfunction "A7_4") (pintype "passive"))
    )
    (net (code "24") (name "/HBRIDGE4_OUT1") (class "Default")
      (node (ref "J3") (pin "1") (pinfunction "1_1") (pintype "passive"))
      (node (ref "U4") (pin "7") (pinfunction "OUT1_7") (pintype "passive"))
    )
    (net (code "25") (name "/HBRIDGE4_OUT2") (class "Default")
      (node (ref "J3") (pin "2") (pinfunction "2_2") (pintype "passive"))
      (node (ref "U4") (pin "5") (pinfunction "OUT2_5") (pintype "passive"))
    )
    (net (code "26") (name "/HBRIDGE4_PH") (class "Default")
      (node (ref "TP10") (pin "TP") (pinfunction "TP_TP") (pintype "passive"))
      (node (ref "U4") (pin "10") (pinfunction "PH/IN2_10") (pintype "input"))
    )
    (net (code "27") (name "/HBRIDGE4_nFAULT") (class "Default")
      (node (ref "R19") (pin "2") (pinfunction "2_2") (pintype "passive"))
      (node (ref "U4") (pin "1") (pinfunction "~{FAULT}_1") (pintype "output"))
      (node (ref "U7") (pin "15") (pinfunction "A2_15") (pintype "passive"))
    )
    (net (code "28") (name "/HBRIDGE5_EN") (class "Default")
      (node (ref "TP11") (pin "TP") (pinfunction "TP_TP") (pintype "passive"))
      (node (ref "U6") (pin "9") (pinfunction "EN/IN1_9") (pintype "input"))
    )
    (net (code "29") (name "/HBRIDGE5_IPROPI") (class "Default")
      (node (ref "R34") (pin "2") (pinfunction "2_2") (pintype "passive"))
      (node (ref "U6") (pin "2") (pinfunction "IPROPI_2") (pintype "bidirectional"))
    )
    (net (code "30") (name "/HBRIDGE5_OUT1") (class "Default")
      (node (ref "J4") (pin "2") (pinfunction "2_2") (pintype "passive"))
      (node (ref "U6") (pin "7") (pinfunction "OUT1_7") (pintype "passive"))
    )
    (net (code "31") (name "/HBRIDGE5_OUT2") (class "Default")
      (node (ref "J4") (pin "1") (pinfunction "1_1") (pintype "passive"))
      (node (ref "U6") (pin "5") (pinfunction "OUT2_5") (pintype "passive"))
    )
    (net (code "32") (name "/HBRIDGE5_PH") (class "Default")
      (node (ref "TP12") (pin "TP") (pinfunction "TP_TP") (pintype "passive"))
      (node (ref "U6") (pin "10") (pinfunction "PH/IN2_10") (pintype "input"))
    )
    (net (code "33") (name "/HBRIDGE5_nFAULT") (class "Default")
      (node (ref "R33") (pin "2") (pinfunction "2_2") (pintype "passive"))
      (node (ref "U6") (pin "1") (pinfunction "~{FAULT}_1") (pintype "output"))
    )
    (net (code "34") (name "/MP_DATA") (class "Default")
      (node (ref "U7") (pin "3") (pinfunction "A_3") (pintype "passive"))
    )
    (net (code "35") (name "/MP_S0") (class "Default")
      (node (ref "U7") (pin "11") (pinfunction "S0_11") (pintype "input"))
    )
    (net (code "36") (name "/MP_S1") (class "Default")
      (node (ref "U7") (pin "10") (pinfunction "S1_10") (pintype "input"))
    )
    (net (code "37") (name "/MP_S2") (class "Default")
      (node (ref "U7") (pin "9") (pinfunction "S2_9") (pintype "input"))
    )
    (net (code "38") (name "/PUMP_PWR") (class "Default")
      (node (ref "J5") (pin "2") (pinfunction "2_2") (pintype "passive"))
      (node (ref "Q5") (pin "D") (pinfunction "D_D") (pintype "passive"))
    )
    (net (code "39") (name "/PUMP_SW") (class "Default")
      (node (ref "Q6") (pin "1") (pinfunction "1_1") (pintype "passive"))
      (node (ref "R39") (pin "2") (pinfunction "2_2") (pintype "passive"))
    )
    (net (code "40") (name "/SERVO_3V3") (class "Default")
      (node (ref "Q3") (pin "2") (pinfunction "E_2") (pintype "passive"))
      (node (ref "Q4") (pin "3") (pinfunction "C_3") (pintype "passive"))
      (node (ref "R31") (pin "2") (pinfunction "2_2") (pintype "passive"))
    )
    (net (code "41") (name "/SERVO_5V") (class "Default")
      (node (ref "J7") (pin "2") (pinfunction "2_2") (pintype "passive"))
      (node (ref "Q3") (pin "3") (pinfunction "C_3") (pintype "passive"))
      (node (ref "Q4") (pin "2") (pinfunction "E_2") (pintype "passive"))
      (node (ref "R32") (pin "2") (pinfunction "2_2") (pintype "passive"))
    )
    (net (code "42") (name "/USB_N") (class "Default")
      (node (ref "J2") (pin "2") (pinfunction "D-_2") (pintype "passive"))
    )
    (net (code "43") (name "/USB_P") (class "Default")
      (node (ref "J2") (pin "3") (pinfunction "D+_3") (pintype "passive"))
    )
    (net (code "44") (name "/nSLEEP") (class "Default")
      (node (ref "TP4") (pin "TP") (pinfunction "TP_TP") (pintype "passive"))
      (node (ref "U1") (pin "3") (pinfunction "~{SLEEP}_3") (pintype "input"))
      (node (ref "U2") (pin "3") (pinfunction "~{SLEEP}_3") (pintype "input"))
      (node (ref "U3") (pin "3") (pinfunction "~{SLEEP}_3") (pintype "input"))
      (node (ref "U4") (pin "3") (pinfunction "~{SLEEP}_3") (pintype "input"))
      (node (ref "U6") (pin "3") (pinfunction "~{SLEEP}_3") (pintype "input"))
    )
    (net (code "45") (name "3V3") (class "Default")
      (node (ref "C11") (pin "1") (pinfunction "1_1") (pintype "passive"))
      (node (ref "C12") (pin "1") (pinfunction "1_1") (pintype "passive"))
      (node (ref "C13") (pin "1") (pinfunction "1_1") (pintype "passive"))
      (node (ref "R18") (pin "1") (pinfunction "1_1") (pintype "passive"))
      (node (ref "R19") (pin "1") (pinfunction "1_1") (pintype "passive"))
      (node (ref "R2") (pin "1") (pinfunction "1_1") (pintype "passive"))
      (node (ref "R3") (pin "1") (pinfunction "1_1") (pintype "passive"))
      (node (ref "R30") (pin "1") (pinfunction "1_1") (pintype "passive"))
      (node (ref "R31") (pin "1") (pinfunction "1_1") (pintype "passive"))
      (node (ref "R33") (pin "1") (pinfunction "1_1") (pintype "passive"))
      (node (ref "R39") (pin "1") (pinfunction "1_1") (pintype "passive"))
      (node (ref "R4") (pin "2") (pinfunction "2_2") (pintype "passive"))
      (node (ref "U5") (pin "2") (pinfunction "VOUT_2_2") (pintype "power_in"))
      (node (ref "U5") (pin "4") (pinfunction "VOUT_4_4") (pintype "power_in"))
    )
    (net (code "46") (name "5V") (class "Default")
      (node (ref "C10") (pin "1") (pinfunction "1_1") (pintype "passive"))
      (node (ref "C16") (pin "2") (pinfunction "2_2") (pintype "passive"))
      (node (ref "J6") (pin "5") (pinfunction "5_5") (pintype "passive"))
      (node (ref "R32") (pin "1") (pinfunction "1_1") (pintype "passive"))
      (node (ref "U5") (pin "3") (pinfunction "VIN_3") (pintype "power_in"))
      (node (ref "U7") (pin "16") (pinfunction "VCC_16") (pintype "power_in"))
    )
    (net (code "47") (name "12V") (class "Default")
      (node (ref "J6") (pin "6") (pinfunction "6_6") (pintype "passive"))
      (node (ref "J7") (pin "1") (pinfunction "1_1") (pintype "passive"))
    )
    (net (code "48") (name "GND") (class "Default")
      (node (ref "C1") (pin "1") (pinfunction "1_1") (pintype "passive"))
      (node (ref "C14") (pin "1") (pinfunction "1_1") (pintype "passive"))
      (node (ref "C15") (pin "2") (pinfunction "2_2") (pintype "passive"))
      (node (ref "C2") (pin "1") (pinfunction "1_1") (pintype "passive"))
      (node (ref "C3") (pin "2") (pinfunction "2_2") (pintype "passive"))
      (node (ref "C4") (pin "2") (pinfunction "2_2") (pintype "passive"))
      (node (ref "C5") (pin "1") (pinfunction "1_1") (pintype "passive"))
      (node (ref "C6") (pin "1") (pinfunction "1_1") (pintype "passive"))
      (node (ref "C7") (pin "1") (pinfunction "1_1") (pintype "passive"))
      (node (ref "C8") (pin "2") (pinfunction "2_2") (pintype "passive"))
      (node (ref "C9") (pin "2") (pinfunction "2_2") (pintype "passive"))
      (node (ref "D2") (pin "2") (pinfunction "2_2") (pintype "passive"))
      (node (ref "J1") (pin "1") (pinfunction "1_1") (pintype "passive"))
      (node (ref "J1") (pin "2") (pinfunction "2_2") (pintype "passive"))
      (node (ref "J1") (pin "3") (pinfunction "3_3") (pintype "passive"))
      (node (ref "J1") (pin "4") (pinfunction "4_4") (pintype "passive"))
      (node (ref "J5") (pin "1") (pinfunction "1_1") (pintype "passive"))
      (node (ref "Q6") (pin "2") (pinfunction "2_2") (pintype "passive"))
      (node (ref "R10") (pin "2") (pinfunction "2_2") (pintype "passive"))
      (node (ref "R11") (pin "2") (pinfunction "2_2") (pintype "passive"))
      (node (ref "R12") (pin "2") (pinfunction "2_2") (pintype "passive"))
      (node (ref "R13") (pin "2") (pinfunction "2_2") (pintype "passive"))
      (node (ref "R14") (pin "2") (pinfunction "2_2") (pintype "passive"))
      (node (ref "R15") (pin "2") (pinfunction "2_2") (pintype "passive"))
      (node (ref "R16") (pin "2") (pinfunction "2_2") (pintype "passive"))
      (node (ref "R17") (pin "2") (pinfunction "2_2") (pintype "passive"))
      (node (ref "R22") (pin "2") (pinfunction "2_2") (pintype "passive"))
      (node (ref "R23") (pin "2") (pinfunction "2_2") (pintype "passive"))
      (node (ref "R24") (pin "2") (pinfunction "2_2") (pintype "passive"))
      (node (ref "R25") (pin "2") (pinfunction "2_2") (pintype "passive"))
      (node (ref "R26") (pin "2") (pinfunction "2_2") (pintype "passive"))
      (node (ref "R27") (pin "2") (pinfunction "2_2") (pintype "passive"))
      (node (ref "R28") (pin "2") (pinfunction "2_2") (pintype "passive"))
      (node (ref "R29") (pin "2") (pinfunction "2_2") (pintype "passive"))
      (node (ref "R9") (pin "2") (pinfunction "2_2") (pintype "passive"))
      (node (ref "U1") (pin "6") (pinfunction "GND_6") (pintype "power_in"))
      (node (ref "U2") (pin "6") (pinfunction "GND_6") (pintype "power_in"))
      (node (ref "U3") (pin "6") (pinfunction "GND_6") (pintype "power_in"))
      (node (ref "U4") (pin "6") (pinfunction "GND_6") (pintype "power_in"))
      (node (ref "U6") (pin "11") (pinfunction "DIAG_11") (pintype "input"))
      (node (ref "U6") (pin "12") (pinfunction "SR_12") (pintype "input"))
      (node (ref "U6") (pin "13") (pinfunction "ITRIP_13") (pintype "input"))
      (node (ref "U6") (pin "14") (pinfunction "MODE_14") (pintype "input"))
      (node (ref "U6") (pin "6") (pinfunction "GND_6") (pintype "power_in"))
    )
    (net (code "49") (name "Net-(C5-Pad2)") (class "Default")
      (node (ref "C5") (pin "2") (pinfunction "2_2") (pintype "passive"))
      (node (ref "D1") (pin "1") (pinfunction "1_1") (pintype "passive"))
      (node (ref "R1") (pin "2") (pinfunction "2_2") (pintype "passive"))
      (node (ref "R6") (pin "1") (pinfunction "1_1") (pintype "passive"))
      (node (ref "R9") (pin "1") (pinfunction "1_1") (pintype "passive"))
    )
    (net (code "50") (name "Net-(D2-Pad1)") (class "Default")
      (node (ref "D2") (pin "1") (pinfunction "1_1") (pintype "passive"))
      (node (ref "R5") (pin "2") (pinfunction "2_2") (pintype "passive"))
    )
    (net (code "51") (name "Net-(D3-Pad1)") (class "Default")
      (node (ref "D3") (pin "1") (pinfunction "1_1") (pintype "passive"))
      (node (ref "R4") (pin "1") (pinfunction "1_1") (pintype "passive"))
    )
    (net (code "52") (name "Net-(F3-Pad2)") (class "Default")
      (node (ref "F3") (pin "2") (pinfunction "2_2") (pintype "passive"))
      (node (ref "Q1") (pin "D") (pinfunction "D_D") (pintype "passive"))
      (node (ref "Q2") (pin "D") (pinfunction "D_D") (pintype "passive"))
    )
    (net (code "53") (name "Net-(Q1-G)") (class "Default")
      (node (ref "Q1") (pin "4") (pinfunction "G_4") (pintype "passive"))
      (node (ref "R1") (pin "1") (pinfunction "1_1") (pintype "passive"))
    )
    (net (code "54") (name "Net-(Q2-G)") (class "Default")
      (node (ref "Q2") (pin "4") (pinfunction "G_4") (pintype "passive"))
      (node (ref "R6") (pin "2") (pinfunction "2_2") (pintype "passive"))
    )
    (net (code "55") (name "Net-(Q3-B)") (class "Default")
      (node (ref "Q3") (pin "1") (pinfunction "B_1") (pintype "passive"))
      (node (ref "Q4") (pin "1") (pinfunction "B_1") (pintype "passive"))
      (node (ref "R30") (pin "2") (pinfunction "2_2") (pintype "passive"))
    )
    (net (code "56") (name "Net-(Q5-G)") (class "Default")
      (node (ref "Q5") (pin "4") (pinfunction "G_4") (pintype "passive"))
      (node (ref "Q6") (pin "3") (pinfunction "3_3") (pintype "passive"))
      (node (ref "R38") (pin "2") (pinfunction "2_2") (pintype "passive"))
    )
    (net (code "57") (name "Net-(U1-DIAG)") (class "Default")
      (node (ref "R16") (pin "1") (pinfunction "1_1") (pintype "passive"))
      (node (ref "U1") (pin "11") (pinfunction "DIAG_11") (pintype "input"))
    )
    (net (code "58") (name "Net-(U1-ITRIP)") (class "Default")
      (node (ref "R12") (pin "1") (pinfunction "1_1") (pintype "passive"))
      (node (ref "U1") (pin "13") (pinfunction "ITRIP_13") (pintype "input"))
    )
    (net (code "59") (name "Net-(U1-MODE)") (class "Default")
      (node (ref "R10") (pin "1") (pinfunction "1_1") (pintype "passive"))
      (node (ref "U1") (pin "14") (pinfunction "MODE_14") (pintype "input"))
    )
    (net (code "60") (name "Net-(U1-SR)") (class "Default")
      (node (ref "R14") (pin "1") (pinfunction "1_1") (pintype "passive"))
      (node (ref "U1") (pin "12") (pinfunction "SR_12") (pintype "input"))
    )
    (net (code "61") (name "Net-(U1-VM)") (class "Default")
      (node (ref "C1") (pin "2") (pinfunction "2_2") (pintype "passive"))
      (node (ref "C3") (pin "1") (pinfunction "1_1") (pintype "passive"))
      (node (ref "F1") (pin "2") (pinfunction "2_2") (pintype "passive"))
      (node (ref "U1") (pin "4") (pinfunction "VM_4") (pintype "power_in"))
    )
    (net (code "62") (name "Net-(U2-DIAG)") (class "Default")
      (node (ref "R17") (pin "1") (pinfunction "1_1") (pintype "passive"))
      (node (ref "U2") (pin "11") (pinfunction "DIAG_11") (pintype "input"))
    )
    (net (code "63") (name "Net-(U2-ITRIP)") (class "Default")
      (node (ref "R13") (pin "1") (pinfunction "1_1") (pintype "passive"))
      (node (ref "U2") (pin "13") (pinfunction "ITRIP_13") (pintype "input"))
    )
    (net (code "64") (name "Net-(U2-MODE)") (class "Default")
      (node (ref "R11") (pin "1") (pinfunction "1_1") (pintype "passive"))
      (node (ref "U2") (pin "14") (pinfunction "MODE_14") (pintype "input"))
    )
    (net (code "65") (name "Net-(U2-SR)") (class "Default")
      (node (ref "R15") (pin "1") (pinfunction "1_1") (pintype "passive"))
      (node (ref "U2") (pin "12") (pinfunction "SR_12") (pintype "input"))
    )
    (net (code "66") (name "Net-(U2-VM)") (class "Default")
      (node (ref "C2") (pin "2") (pinfunction "2_2") (pintype "passive"))
      (node (ref "C4") (pin "1") (pinfunction "1_1") (pintype "passive"))
      (node (ref "F2") (pin "2") (pinfunction "2_2") (pintype "passive"))
      (node (ref "U2") (pin "4") (pinfunction "VM_4") (pintype "power_in"))
    )
    (net (code "67") (name "Net-(U3-DIAG)") (class "Default")
      (node (ref "R28") (pin "1") (pinfunction "1_1") (pintype "passive"))
      (node (ref "U3") (pin "11") (pinfunction "DIAG_11") (pintype "input"))
    )
    (net (code "68") (name "Net-(U3-ITRIP)") (class "Default")
      (node (ref "R24") (pin "1") (pinfunction "1_1") (pintype "passive"))
      (node (ref "U3") (pin "13") (pinfunction "ITRIP_13") (pintype "input"))
    )
    (net (code "69") (name "Net-(U3-MODE)") (class "Default")
      (node (ref "R22") (pin "1") (pinfunction "1_1") (pintype "passive"))
      (node (ref "U3") (pin "14") (pinfunction "MODE_14") (pintype "input"))
    )
    (net (code "70") (name "Net-(U3-SR)") (class "Default")
      (node (ref "R26") (pin "1") (pinfunction "1_1") (pintype "passive"))
      (node (ref "U3") (pin "12") (pinfunction "SR_12") (pintype "input"))
    )
    (net (code "71") (name "Net-(U3-VM)") (class "Default")
      (node (ref "C6") (pin "2") (pinfunction "2_2") (pintype "passive"))
      (node (ref "C8") (pin "1") (pinfunction "1_1") (pintype "passive"))
      (node (ref "F4") (pin "2") (pinfunction "2_2") (pintype "passive"))
      (node (ref "U3") (pin "4") (pinfunction "VM_4") (pintype "power_in"))
    )
    (net (code "72") (name "Net-(U4-DIAG)") (class "Default")
      (node (ref "R29") (pin "1") (pinfunction "1_1") (pintype "passive"))
      (node (ref "U4") (pin "11") (pinfunction "DIAG_11") (pintype "input"))
    )
    (net (code "73") (name "Net-(U4-ITRIP)") (class "Default")
      (node (ref "R25") (pin "1") (pinfunction "1_1") (pintype "passive"))
      (node (ref "U4") (pin "13") (pinfunction "ITRIP_13") (pintype "input"))
    )
    (net (code "74") (name "Net-(U4-MODE)") (class "Default")
      (node (ref "R23") (pin "1") (pinfunction "1_1") (pintype "passive"))
      (node (ref "U4") (pin "14") (pinfunction "MODE_14") (pintype "input"))
    )
    (net (code "75") (name "Net-(U4-SR)") (class "Default")
      (node (ref "R27") (pin "1") (pinfunction "1_1") (pintype "passive"))
      (node (ref "U4") (pin "12") (pinfunction "SR_12") (pintype "input"))
    )
    (net (code "76") (name "Net-(U4-VM)") (class "Default")
      (node (ref "C7") (pin "2") (pinfunction "2_2") (pintype "passive"))
      (node (ref "C9") (pin "1") (pinfunction "1_1") (pintype "passive"))
      (node (ref "F5") (pin "2") (pinfunction "2_2") (pintype "passive"))
      (node (ref "U4") (pin "4") (pinfunction "VM_4") (pintype "power_in"))
    )
    (net (code "77") (name "Net-(U6-VM)") (class "Default")
      (node (ref "C14") (pin "2") (pinfunction "2_2") (pintype "passive"))
      (node (ref "C15") (pin "1") (pinfunction "1_1") (pintype "passive"))
      (node (ref "F6") (pin "2") (pinfunction "2_2") (pintype "passive"))
      (node (ref "U6") (pin "4") (pinfunction "VM_4") (pintype "power_in"))
    )
    (net (code "78") (name "VCC") (class "Default")
      (node (ref "D1") (pin "2") (pinfunction "2_2") (pintype "passive"))
      (node (ref "F1") (pin "1") (pinfunction "1_1") (pintype "passive"))
      (node (ref "F2") (pin "1") (pinfunction "1_1") (pintype "passive"))
      (node (ref "F4") (pin "1") (pinfunction "1_1") (pintype "passive"))
      (node (ref "F5") (pin "1") (pinfunction "1_1") (pintype "passive"))
      (node (ref "F6") (pin "1") (pinfunction "1_1") (pintype "passive"))
      (node (ref "Q1") (pin "1") (pinfunction "S_1") (pintype "passive"))
      (node (ref "Q1") (pin "2") (pinfunction "S_2") (pintype "passive"))
      (node (ref "Q1") (pin "3") (pinfunction "S_3") (pintype "passive"))
      (node (ref "Q2") (pin "1") (pinfunction "S_1") (pintype "passive"))
      (node (ref "Q2") (pin "2") (pinfunction "S_2") (pintype "passive"))
      (node (ref "Q2") (pin "3") (pinfunction "S_3") (pintype "passive"))
      (node (ref "Q5") (pin "1") (pinfunction "S_1") (pintype "passive"))
      (node (ref "Q5") (pin "2") (pinfunction "S_2") (pintype "passive"))
      (node (ref "Q5") (pin "3") (pinfunction "S_3") (pintype "passive"))
      (node (ref "R38") (pin "1") (pinfunction "1_1") (pintype "passive"))
      (node (ref "R5") (pin "1") (pinfunction "1_1") (pintype "passive"))
    )
    (net (code "79") (name "VIN") (class "Default")
      (node (ref "F3") (pin "1") (pinfunction "1_1") (pintype "passive"))
      (node (ref "J1") (pin "5") (pinfunction "5_5") (pintype "passive"))
      (node (ref "J1") (pin "6") (pinfunction "6_6") (pintype "passive"))
      (node (ref "J1") (pin "7") (pinfunction "7_7") (pintype "passive"))
      (node (ref "J1") (pin "8") (pinfunction "8_8") (pintype "passive"))
      (node (ref "J6") (pin "3") (pinfunction "3_3") (pintype "passive"))
    )
    (net (code "80") (name "dGND") (class "Default")
      (node (ref "C10") (pin "2") (pinfunction "2_2") (pintype "passive"))
      (node (ref "C11") (pin "2") (pinfunction "2_2") (pintype "passive"))
      (node (ref "C12") (pin "2") (pinfunction "2_2") (pintype "passive"))
      (node (ref "C13") (pin "2") (pinfunction "2_2") (pintype "passive"))
      (node (ref "C16") (pin "1") (pinfunction "1_1") (pintype "passive"))
      (node (ref "D3") (pin "2") (pinfunction "2_2") (pintype "passive"))
      (node (ref "J2") (pin "5") (pinfunction "GND_5") (pintype "passive"))
      (node (ref "J2") (pin "6") (pinfunction "S_GND_6") (pintype "passive"))
      (node (ref "J2") (pin "7") (pinfunction "S_GND_7") (pintype "passive"))
      (node (ref "J2") (pin "8") (pinfunction "S_GND_8") (pintype "passive"))
      (node (ref "J2") (pin "9") (pinfunction "S_GND_9") (pintype "passive"))
      (node (ref "J6") (pin "2") (pinfunction "2_2") (pintype "passive"))
      (node (ref "J7") (pin "3") (pinfunction "3_3") (pintype "passive"))
      (node (ref "J7") (pin "4") (pinfunction "4_4") (pintype "passive"))
      (node (ref "R20") (pin "1") (pinfunction "1_1") (pintype "passive"))
      (node (ref "R21") (pin "1") (pinfunction "1_1") (pintype "passive"))
      (node (ref "R34") (pin "1") (pinfunction "1_1") (pintype "passive"))
      (node (ref "R7") (pin "1") (pinfunction "1_1") (pintype "passive"))
      (node (ref "R8") (pin "1") (pinfunction "1_1") (pintype "passive"))
      (node (ref "U5") (pin "1") (pinfunction "GND_1") (pintype "power_in"))
      (node (ref "U7") (pin "6") (pinfunction "~{E}_6") (pintype "input"))
      (node (ref "U7") (pin "7") (pinfunction "VEE_7") (pintype "power_in"))
      (node (ref "U7") (pin "8") (pinfunction "GND_8") (pintype "power_in"))
    )
    (net (code "81") (name "unconnected-(J2-ID-Pad4)") (class "Default")
      (node (ref "J2") (pin "4") (pinfunction "ID_4") (pintype "passive"))
    )
    (net (code "82") (name "unconnected-(J2-VCC-Pad1)") (class "Default")
      (node (ref "J2") (pin "1") (pinfunction "VCC_1") (pintype "passive"))
    )
  )
)
